# SCH.net
KiCad netlist of a schematic drawn in Altium Designer
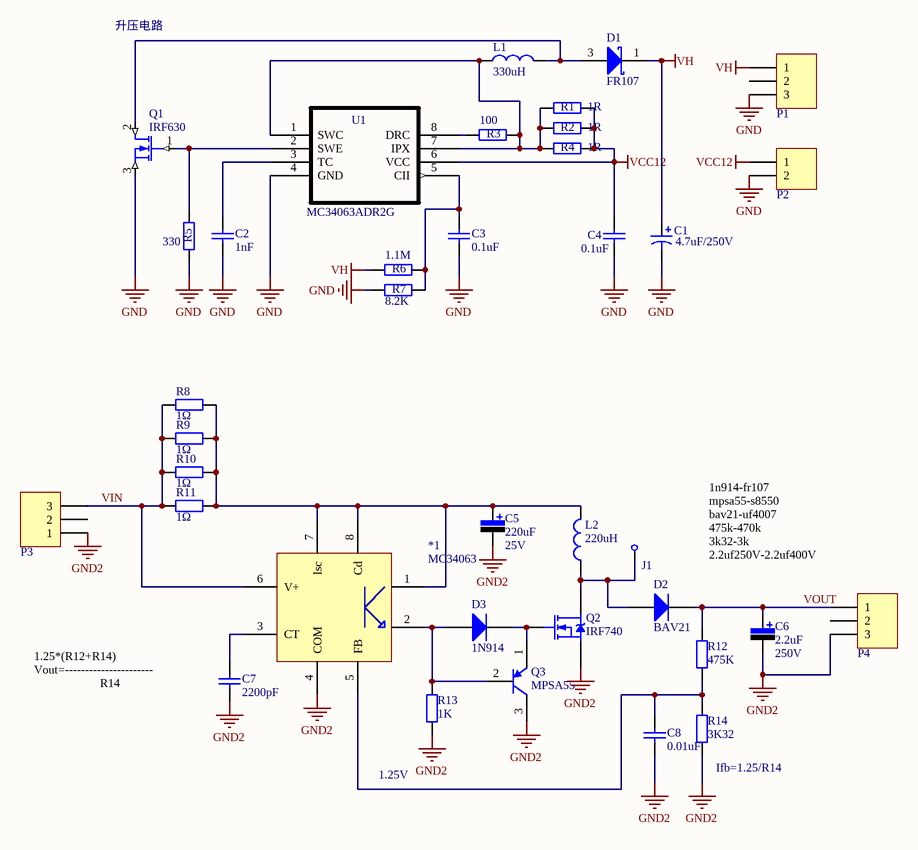
[diagram p0: SCH.SchDoc]

(export (version "E")
  (design (tool "Eeschema 10.0.6"))
  (components
    (comp (ref "*1") (value "MC34063") (footprint "SOP-8") (libsource (lib "fszhang") (part "MC34063")))
    (comp (ref "C1")
      (value "4.7uF/250V")
      (footprint "1812")
      (description "Polarized Capacitor (Surface Mount)")
      (fields (field (name "Comment") "Cap Pol3") (field (name "PUBLISHER") "Altium Limited"))
      (libsource (lib "Miscellaneous Devices") (part "Cap Pol3"))
    )
    (comp (ref "C2")
      (value "1nF")
      (footprint "0805")
      (description "Capacitor")
      (fields (field (name "Comment") "Cap") (field (name "PUBLISHER") "Altium Limited"))
      (libsource (lib "Miscellaneous Devices") (part "Cap"))
    )
    (comp (ref "C3")
      (value "0.1uF")
      (footprint "0805")
      (description "Capacitor")
      (fields (field (name "Comment") "Cap") (field (name "PUBLISHER") "Altium Limited"))
      (libsource (lib "Miscellaneous Devices") (part "Cap"))
    )
    (comp (ref "C4")
      (value "0.1uF")
      (footprint "0805")
      (description "Capacitor")
      (fields (field (name "Comment") "Cap") (field (name "PUBLISHER") "Altium Limited"))
      (libsource (lib "Miscellaneous Devices") (part "Cap"))
    )
    (comp (ref "C5")
      (value "220uF")
      (footprint "C-RB-6")
      (description "极性电解电容")
      (fields
        (field (name "VOL") "25V")
        (field (name "Comment") "Cap Pol")
        (field (name "PUBLISHER") "Altium Limited")
      )
      (libsource (lib "fszhang") (part "Cap Pol"))
    )
    (comp (ref "C6")
      (value "2.2uF")
      (footprint "C-RB-8")
      (description "极性电解电容")
      (fields
        (field (name "VOL") "250V")
        (field (name "Comment") "Cap Pol")
        (field (name "PUBLISHER") "Altium Limited")
      )
      (libsource (lib "fszhang") (part "Cap Pol"))
    )
    (comp (ref "C7")
      (value "2200pF")
      (footprint "C-RAD-0805")
      (description "无极性电容")
      (fields (field (name "Comment") "Cap") (field (name "PUBLISHER") "Altium Limited"))
      (libsource (lib "fszhang") (part "Cap"))
    )
    (comp (ref "C8")
      (value "0.01uF")
      (footprint "C-RAD-0805")
      (description "无极性电容")
      (fields (field (name "Comment") "Cap") (field (name "PUBLISHER") "Altium Limited"))
      (libsource (lib "fszhang") (part "Cap"))
    )
    (comp (ref "D1")
      (value "FR107")
      (footprint "DO-214AC")
      (description "Schottky Rectifier")
      (fields (field (name "PUBLISHER") "Altium Limited"))
      (libsource (lib "Miscellaneous Devices") (part "Diode 18TQ045"))
    )
    (comp (ref "D2")
      (value "Diode")
      (footprint "DO-35")
      (description "二极管")
      (fields (field (name "TYPE") "BAV21") (field (name "PUBLISHER") "Altium Limited"))
      (libsource (lib "fszhang") (part "Diode"))
    )
    (comp (ref "D3")
      (value "Diode")
      (footprint "DIODE-SMA")
      (description "二极管")
      (fields (field (name "TYPE") "1N914") (field (name "PUBLISHER") "Altium Limited"))
      (libsource (lib "fszhang") (part "Diode"))
    )
    (comp (ref "J1")
      (value "CHECK")
      (footprint "CHECK-A")
      (description "测试点")
      (libsource (lib "fszhang") (part "CHECK"))
    )
    (comp (ref "L1") (value "330uH") (footprint "330uH") (libsource (lib "SCH") (part "L")))
    (comp (ref "L2")
      (value "220uH")
      (footprint "L-SMD-7")
      (description "电感")
      (fields (field (name "Comment") "Inductor") (field (name "PUBLISHER") "Altium Limited"))
      (libsource (lib "fszhang") (part "Inductor"))
    )
    (comp (ref "P1")
      (value "Header 3")
      (footprint "HDR3X1_A")
      (description "接插件")
      (fields (field (name "PUBLISHER") "Altium Limited"))
      (libsource (lib "") (part "Header 3_1"))
    )
    (comp (ref "P2")
      (value "Header 2")
      (footprint "HDR2X1_A")
      (description "接插件")
      (fields (field (name "PUBLISHER") "Altium Limited"))
      (libsource (lib "fszhang") (part "Header 2"))
    )
    (comp (ref "P3")
      (value "Header 3")
      (footprint "HDR3X1_A")
      (description "接插件")
      (fields (field (name "PUBLISHER") "Altium Limited"))
      (libsource (lib "fszhang") (part "Header 3"))
    )
    (comp (ref "P4")
      (value "Header 3")
      (footprint "HDR3X1_A")
      (description "接插件")
      (fields (field (name "PUBLISHER") "Altium Limited"))
      (libsource (lib "") (part "Header 3_1"))
    )
    (comp (ref "Q1")
      (value "IRF630")
      (footprint "TO-263")
      (description "N-Channel MOSFET")
      (libsource (lib "SCH") (part "IRF630"))
    )
    (comp (ref "Q2")
      (value "IRF740")
      (footprint "TO-220AB")
      (description "N-Channel MOSFET")
      (fields (field (name "PUBLISHER") "Altium Limited"))
      (libsource (lib "fszhang") (part "MOSFET-N"))
    )
    (comp (ref "Q3")
      (value "MPSA55")
      (footprint "TO-92A")
      (description "PNP三极管")
      (fields (field (name "PUBLISHER") "Altium Limited"))
      (libsource (lib "fszhang") (part "S8550"))
    )
    (comp (ref "R1")
      (value "1R")
      (footprint "0805")
      (description "Resistor")
      (fields (field (name "Comment") "Res2") (field (name "PUBLISHER") "Altium Limited"))
      (libsource (lib "Miscellaneous Devices") (part "Res2"))
    )
    (comp (ref "R2")
      (value "1R")
      (footprint "0805")
      (description "Resistor")
      (fields (field (name "Comment") "Res2") (field (name "PUBLISHER") "Altium Limited"))
      (libsource (lib "Miscellaneous Devices") (part "Res2"))
    )
    (comp (ref "R3")
      (value "100")
      (footprint "0805")
      (description "Resistor")
      (fields (field (name "Comment") "Res2") (field (name "PUBLISHER") "Altium Limited"))
      (libsource (lib "") (part "Res2_2"))
    )
    (comp (ref "R4")
      (value "1R")
      (footprint "0805")
      (description "Resistor")
      (fields (field (name "Comment") "Res2") (field (name "PUBLISHER") "Altium Limited"))
      (libsource (lib "Miscellaneous Devices") (part "Res2"))
    )
    (comp (ref "R5")
      (value "330")
      (footprint "0805")
      (description "Resistor")
      (fields (field (name "Comment") "Res2") (field (name "PUBLISHER") "Altium Limited"))
      (libsource (lib "") (part "Res2_1"))
    )
    (comp (ref "R6")
      (value "1.1M")
      (footprint "0805")
      (description "Resistor")
      (fields (field (name "Comment") "Res2") (field (name "PUBLISHER") "Altium Limited"))
      (libsource (lib "Miscellaneous Devices") (part "Res2"))
    )
    (comp (ref "R7")
      (value "8.2K")
      (footprint "0805")
      (description "Resistor")
      (fields (field (name "Comment") "Res2") (field (name "PUBLISHER") "Altium Limited"))
      (libsource (lib "Miscellaneous Devices") (part "Res2"))
    )
    (comp (ref "R8")
      (value "1Ω")
      (footprint "0805-1")
      (description "贴片电阻")
      (fields (field (name "Comment") "Res1") (field (name "PUBLISHER") "Altium Limited"))
      (libsource (lib "fszhang") (part "Res1"))
    )
    (comp (ref "R9")
      (value "1Ω")
      (footprint "0805-1")
      (description "贴片电阻")
      (fields (field (name "Comment") "Res1") (field (name "PUBLISHER") "Altium Limited"))
      (libsource (lib "fszhang") (part "Res1"))
    )
    (comp (ref "R10")
      (value "1Ω")
      (footprint "0805-1")
      (description "贴片电阻")
      (fields (field (name "Comment") "Res1") (field (name "PUBLISHER") "Altium Limited"))
      (libsource (lib "fszhang") (part "Res1"))
    )
    (comp (ref "R11")
      (value "1Ω")
      (footprint "0805-1")
      (description "贴片电阻")
      (fields (field (name "Comment") "Res1") (field (name "PUBLISHER") "Altium Limited"))
      (libsource (lib "fszhang") (part "Res1"))
    )
    (comp (ref "R12")
      (value "475K")
      (footprint "0805-1")
      (description "贴片电阻")
      (fields (field (name "Comment") "Res1") (field (name "PUBLISHER") "Altium Limited"))
      (libsource (lib "") (part "Res1_1"))
    )
    (comp (ref "R13")
      (value "1K")
      (footprint "0805-1")
      (description "贴片电阻")
      (fields (field (name "Comment") "Res1") (field (name "PUBLISHER") "Altium Limited"))
      (libsource (lib "") (part "Res1_1"))
    )
    (comp (ref "R14")
      (value "3K32")
      (footprint "0805-1")
      (description "贴片电阻")
      (fields (field (name "Comment") "Res1") (field (name "PUBLISHER") "Altium Limited"))
      (libsource (lib "") (part "Res1_1"))
    )
    (comp (ref "U1")
      (value "MC34063ADR2G")
      (footprint "SO-8-M")
      (description "Imported")
      (libsource (lib "SCH") (part "MC34063ACD-TR"))
    )
  )
  (nets
    (net (code "1") (name "/VIN") (class "Default")
      (node (ref "*1") (pin "6") (pinfunction "V+_6") (pintype "passive"))
      (node (ref "P3") (pin "3") (pinfunction "3_3") (pintype "passive"))
      (node (ref "R10") (pin "1") (pinfunction "1_1") (pintype "passive"))
      (node (ref "R11") (pin "1") (pinfunction "1_1") (pintype "passive"))
      (node (ref "R8") (pin "1") (pinfunction "1_1") (pintype "passive"))
      (node (ref "R9") (pin "1") (pinfunction "1_1") (pintype "passive"))
    )
    (net (code "2") (name "/VOUT") (class "Default")
      (node (ref "C6") (pin "1") (pinfunction "1_1") (pintype "passive"))
      (node (ref "D2") (pin "2") (pinfunction "K_2") (pintype "passive"))
      (node (ref "P4") (pin "1") (pinfunction "1_1") (pintype "passive"))
      (node (ref "R12") (pin "2") (pinfunction "2_2") (pintype "passive"))
    )
    (net (code "3") (name "GND") (class "Default")
      (node (ref "C1") (pin "2") (pinfunction "2_2") (pintype "passive"))
      (node (ref "C2") (pin "1") (pinfunction "1_1") (pintype "passive"))
      (node (ref "C3") (pin "1") (pinfunction "1_1") (pintype "passive"))
      (node (ref "C4") (pin "1") (pinfunction "1_1") (pintype "passive"))
      (node (ref "P1") (pin "3") (pinfunction "3_3") (pintype "passive"))
      (node (ref "P2") (pin "2") (pinfunction "2_2") (pintype "passive"))
      (node (ref "Q1") (pin "3") (pinfunction "S_3") (pintype "input"))
      (node (ref "R5") (pin "1") (pinfunction "1_1") (pintype "passive"))
      (node (ref "R7") (pin "1") (pinfunction "1_1") (pintype "passive"))
      (node (ref "U1") (pin "4") (pinfunction "GND_4") (pintype "power_in"))
    )
    (net (code "4") (name "GND2") (class "Default")
      (node (ref "*1") (pin "4") (pinfunction "COM_4") (pintype "passive"))
      (node (ref "C5") (pin "2") (pinfunction "2_2") (pintype "passive"))
      (node (ref "C6") (pin "2") (pinfunction "2_2") (pintype "passive"))
      (node (ref "C7") (pin "1") (pinfunction "1_1") (pintype "passive"))
      (node (ref "C8") (pin "1") (pinfunction "1_1") (pintype "passive"))
      (node (ref "P3") (pin "1") (pinfunction "1_1") (pintype "passive"))
      (node (ref "P4") (pin "3") (pinfunction "3_3") (pintype "passive"))
      (node (ref "Q2") (pin "S") (pinfunction "S_S") (pintype "passive"))
      (node (ref "Q3") (pin "3") (pinfunction "C_3") (pintype "passive"))
      (node (ref "R13") (pin "1") (pinfunction "1_1") (pintype "passive"))
      (node (ref "R14") (pin "1") (pinfunction "1_1") (pintype "passive"))
    )
    (net (code "5") (name "Net-(*1-CT)") (class "Default")
      (node (ref "*1") (pin "3") (pinfunction "CT_3") (pintype "passive"))
      (node (ref "C7") (pin "2") (pinfunction "2_2") (pintype "passive"))
    )
    (net (code "6") (name "Net-(*1-Cd)") (class "Default")
      (node (ref "*1") (pin "1") (pinfunction "1_1") (pintype "passive"))
      (node (ref "*1") (pin "7") (pinfunction "Isc_7") (pintype "passive"))
      (node (ref "*1") (pin "8") (pinfunction "Cd_8") (pintype "passive"))
      (node (ref "C5") (pin "1") (pinfunction "1_1") (pintype "passive"))
      (node (ref "L2") (pin "2") (pinfunction "2_2") (pintype "passive"))
      (node (ref "R10") (pin "2") (pinfunction "2_2") (pintype "passive"))
      (node (ref "R11") (pin "2") (pinfunction "2_2") (pintype "passive"))
      (node (ref "R8") (pin "2") (pinfunction "2_2") (pintype "passive"))
      (node (ref "R9") (pin "2") (pinfunction "2_2") (pintype "passive"))
    )
    (net (code "7") (name "Net-(*1-FB)") (class "Default")
      (node (ref "*1") (pin "5") (pinfunction "FB_5") (pintype "passive"))
      (node (ref "C8") (pin "2") (pinfunction "2_2") (pintype "passive"))
      (node (ref "R12") (pin "1") (pinfunction "1_1") (pintype "passive"))
      (node (ref "R14") (pin "2") (pinfunction "2_2") (pintype "passive"))
    )
    (net (code "8") (name "Net-(D1-A)") (class "Default")
      (node (ref "D1") (pin "3") (pinfunction "A_3") (pintype "passive"))
      (node (ref "L1") (pin "1") (pintype "passive"))
      (node (ref "Q1") (pin "2") (pinfunction "D_2") (pintype "input"))
    )
    (net (code "9") (name "Net-(D2-A)") (class "Default")
      (node (ref "D2") (pin "1") (pinfunction "A_1") (pintype "passive"))
      (node (ref "J1") (pin "1") (pinfunction "1_1") (pintype "passive"))
      (node (ref "L2") (pin "1") (pinfunction "1_1") (pintype "passive"))
      (node (ref "Q2") (pin "D") (pinfunction "D_D") (pintype "passive"))
    )
    (net (code "10") (name "Net-(D3-A)") (class "Default")
      (node (ref "*1") (pin "2") (pinfunction "2_2") (pintype "passive"))
      (node (ref "D3") (pin "1") (pinfunction "A_1") (pintype "passive"))
      (node (ref "Q3") (pin "2") (pinfunction "B_2") (pintype "passive"))
      (node (ref "R13") (pin "2") (pinfunction "2_2") (pintype "passive"))
    )
    (net (code "11") (name "Net-(D3-K)") (class "Default")
      (node (ref "D3") (pin "2") (pinfunction "K_2") (pintype "passive"))
      (node (ref "Q2") (pin "G") (pinfunction "G_G") (pintype "passive"))
      (node (ref "Q3") (pin "1") (pinfunction "E_1") (pintype "passive"))
    )
    (net (code "12") (name "Net-(Q1-G)") (class "Default")
      (node (ref "Q1") (pin "1") (pinfunction "G_1") (pintype "input"))
      (node (ref "R5") (pin "2") (pinfunction "2_2") (pintype "passive"))
      (node (ref "U1") (pin "2") (pinfunction "SWE_2") (pintype "passive"))
    )
    (net (code "13") (name "Net-(U1-CII)") (class "Default")
      (node (ref "C3") (pin "2") (pinfunction "2_2") (pintype "passive"))
      (node (ref "R6") (pin "2") (pinfunction "2_2") (pintype "passive"))
      (node (ref "R7") (pin "2") (pinfunction "2_2") (pintype "passive"))
      (node (ref "U1") (pin "5") (pinfunction "CII_5") (pintype "output"))
    )
    (net (code "14") (name "Net-(U1-DRC)") (class "Default")
      (node (ref "R3") (pin "2") (pinfunction "2_2") (pintype "passive"))
      (node (ref "U1") (pin "8") (pinfunction "DRC_8") (pintype "passive"))
    )
    (net (code "15") (name "Net-(U1-IPX)") (class "Default")
      (node (ref "L1") (pin "2") (pintype "passive"))
      (node (ref "R1") (pin "1") (pinfunction "1_1") (pintype "passive"))
      (node (ref "R2") (pin "1") (pinfunction "1_1") (pintype "passive"))
      (node (ref "R3") (pin "1") (pinfunction "1_1") (pintype "passive"))
      (node (ref "R4") (pin "1") (pinfunction "1_1") (pintype "passive"))
      (node (ref "U1") (pin "1") (pinfunction "SWC_1") (pintype "passive"))
      (node (ref "U1") (pin "7") (pinfunction "IPX_7") (pintype "passive"))
    )
    (net (code "16") (name "Net-(U1-TC)") (class "Default")
      (node (ref "C2") (pin "2") (pinfunction "2_2") (pintype "passive"))
      (node (ref "U1") (pin "3") (pinfunction "TC_3") (pintype "passive"))
    )
    (net (code "17") (name "VCC12") (class "Default")
      (node (ref "C4") (pin "2") (pinfunction "2_2") (pintype "passive"))
      (node (ref "P2") (pin "1") (pinfunction "1_1") (pintype "passive"))
      (node (ref "R1") (pin "2") (pinfunction "2_2") (pintype "passive"))
      (node (ref "R2") (pin "2") (pinfunction "2_2") (pintype "passive"))
      (node (ref "R4") (pin "2") (pinfunction "2_2") (pintype "passive"))
      (node (ref "U1") (pin "6") (pinfunction "VCC_6") (pintype "power_in"))
    )
    (net (code "18") (name "VH") (class "Default")
      (node (ref "C1") (pin "1") (pinfunction "1_1") (pintype "passive"))
      (node (ref "D1") (pin "1") (pinfunction "K_1") (pintype "passive"))
      (node (ref "P1") (pin "1") (pinfunction "1_1") (pintype "passive"))
      (node (ref "R6") (pin "1") (pinfunction "1_1") (pintype "passive"))
    )
    (net (code "19") (name "unconnected-(P1-Pad2)") (class "Default")
      (node (ref "P1") (pin "2") (pinfunction "2_2") (pintype "passive"))
    )
    (net (code "20") (name "unconnected-(P3-Pad2)") (class "Default")
      (node (ref "P3") (pin "2") (pinfunction "2_2") (pintype "passive"))
    )
    (net (code "21") (name "unconnected-(P4-Pad2)") (class "Default")
      (node (ref "P4") (pin "2") (pinfunction "2_2") (pintype "passive"))
    )
  )
)
